# R2P_Proximity_module.net
KiCad netlist of a schematic drawn in EAGLE
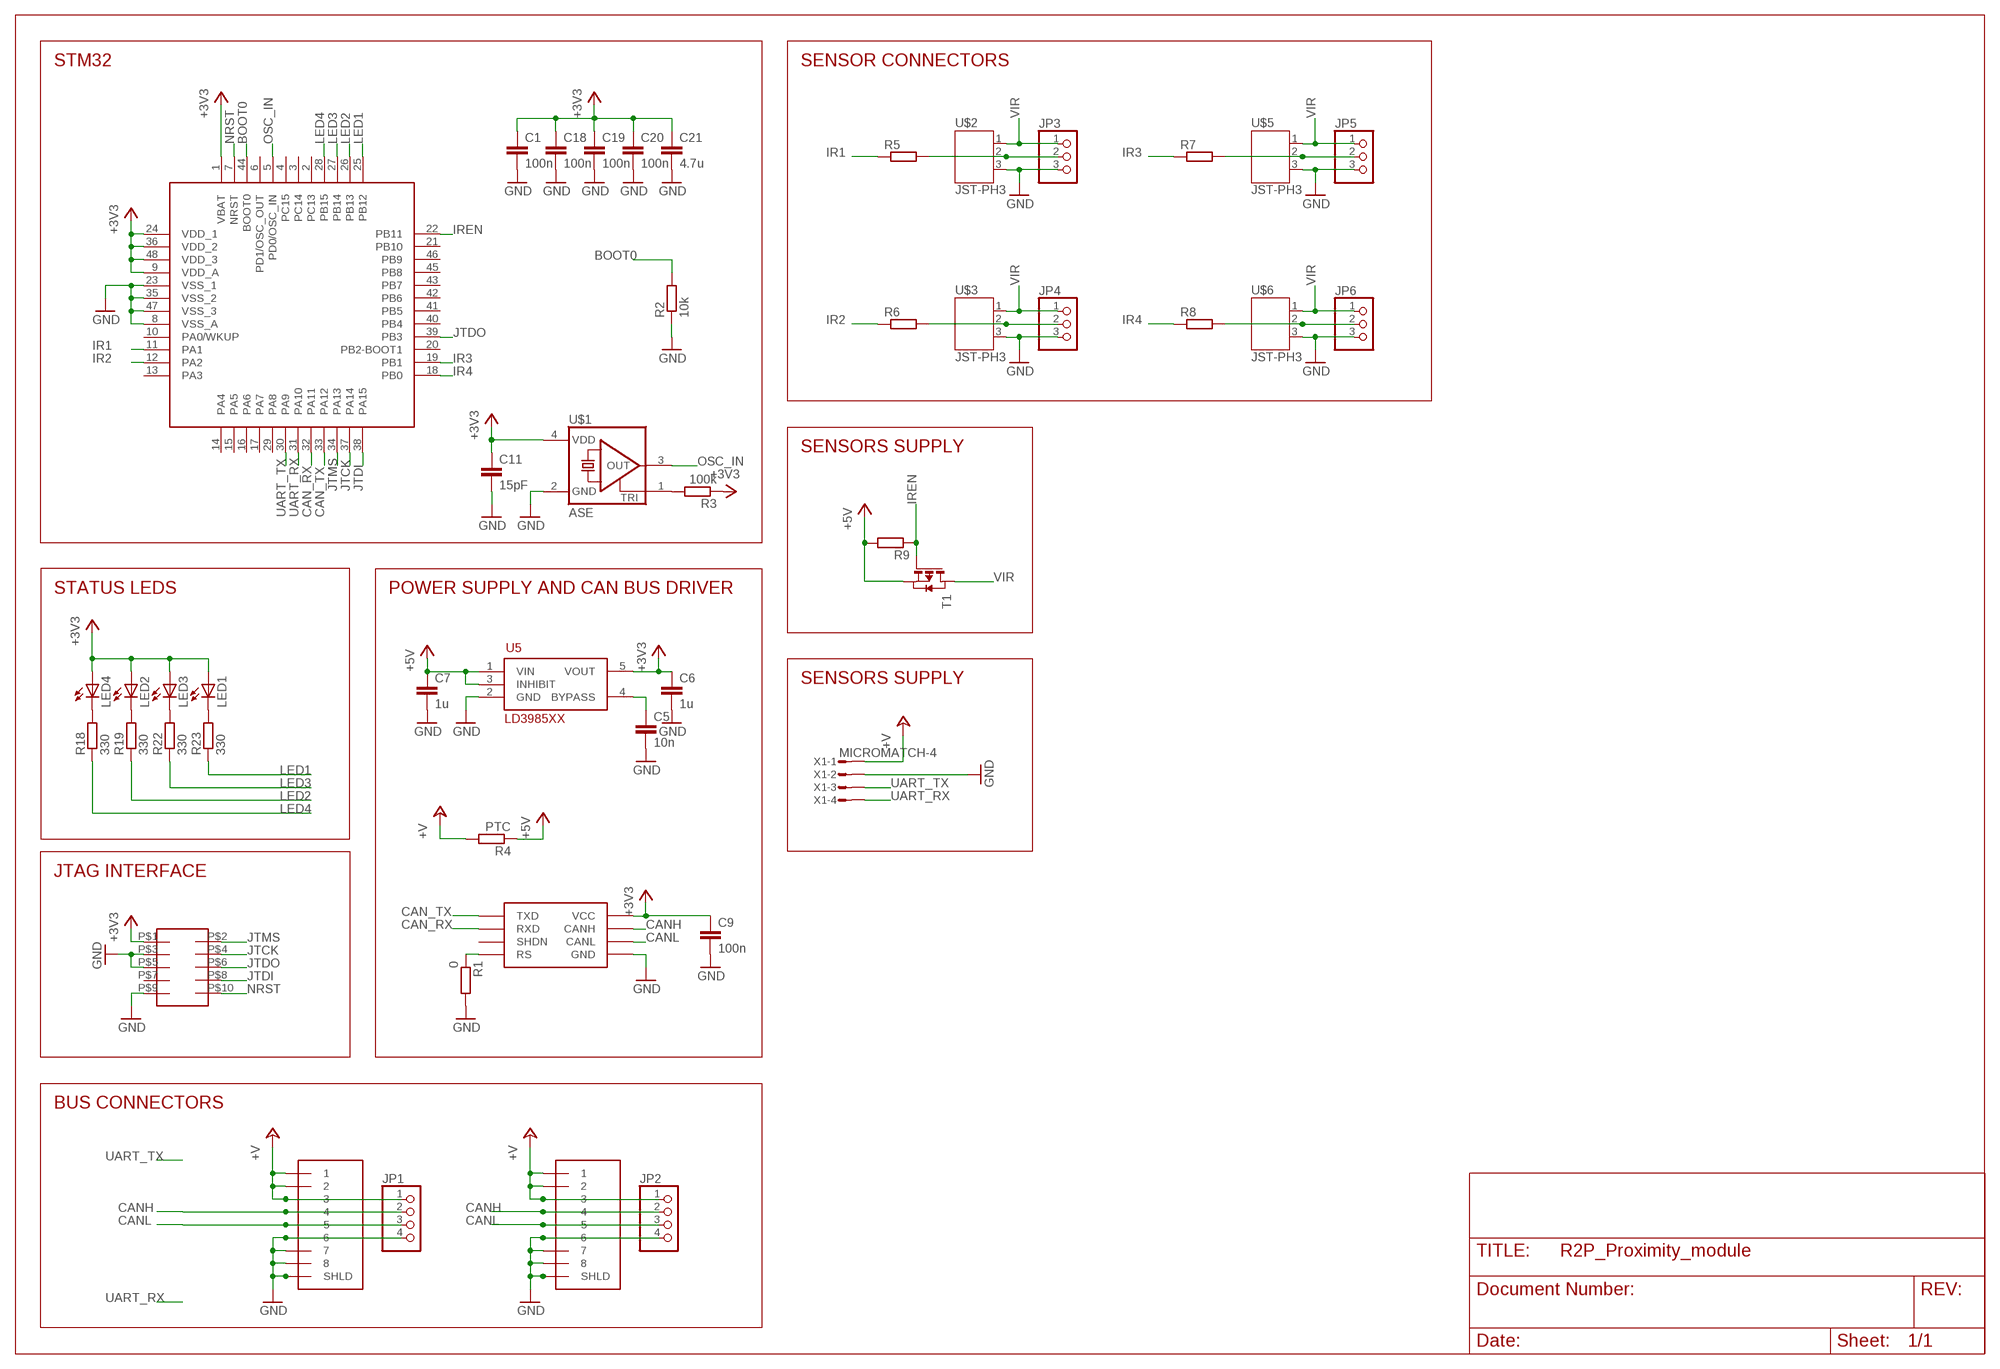
[diagram p0: schematic, sheet 1]

(export (version "E")
  (design (tool "Eeschema 10.0.6"))
  (components
    (comp (ref "1")
      (value "RJ45-43860")
      (footprint "eagle-import:0438600010")
      (libsource (lib "eagle-import") (part "RJ45-43860"))
    )
    (comp (ref "2")
      (value "RJ45-43860")
      (footprint "eagle-import:0438600010")
      (libsource (lib "eagle-import") (part "RJ45-43860"))
    )
    (comp (ref "C1")
      (value "100n")
      (footprint "eagle-import:C0603")
      (libsource (lib "eagle-import") (part "C-EUC0603"))
    )
    (comp (ref "C5")
      (value "10n")
      (footprint "eagle-import:C0603")
      (libsource (lib "eagle-import") (part "C-EUC0603"))
    )
    (comp (ref "C6")
      (value "1u")
      (footprint "eagle-import:C0603")
      (libsource (lib "eagle-import") (part "C-EUC0603"))
    )
    (comp (ref "C7")
      (value "1u")
      (footprint "eagle-import:C0603")
      (libsource (lib "eagle-import") (part "C-EUC0603"))
    )
    (comp (ref "C9")
      (value "100n")
      (footprint "eagle-import:C0603")
      (libsource (lib "eagle-import") (part "C-EUC0603"))
    )
    (comp (ref "C11")
      (value "15pF")
      (footprint "eagle-import:C0603")
      (libsource (lib "eagle-import") (part "C-EUC0603"))
    )
    (comp (ref "C18")
      (value "100n")
      (footprint "eagle-import:C0603")
      (libsource (lib "eagle-import") (part "C-EUC0603"))
    )
    (comp (ref "C19")
      (value "100n")
      (footprint "eagle-import:C0603")
      (libsource (lib "eagle-import") (part "C-EUC0603"))
    )
    (comp (ref "C20")
      (value "100n")
      (footprint "eagle-import:C0603")
      (libsource (lib "eagle-import") (part "C-EUC0603"))
    )
    (comp (ref "C21")
      (value "4.7u")
      (footprint "eagle-import:C0805")
      (libsource (lib "eagle-import") (part "C-EUC0805"))
    )
    (comp (ref "JP1")
      (value "PINHD-1X4")
      (footprint "eagle-import:1X04")
      (libsource (lib "eagle-import") (part "PINHD-1X4"))
    )
    (comp (ref "JP2")
      (value "PINHD-1X4")
      (footprint "eagle-import:1X04")
      (libsource (lib "eagle-import") (part "PINHD-1X4"))
    )
    (comp (ref "JP3")
      (value "PINHD-1X3")
      (footprint "eagle-import:1X03")
      (libsource (lib "eagle-import") (part "PINHD-1X3"))
    )
    (comp (ref "JP4")
      (value "PINHD-1X3")
      (footprint "eagle-import:1X03")
      (libsource (lib "eagle-import") (part "PINHD-1X3"))
    )
    (comp (ref "JP5")
      (value "PINHD-1X3")
      (footprint "eagle-import:1X03")
      (libsource (lib "eagle-import") (part "PINHD-1X3"))
    )
    (comp (ref "JP6")
      (value "PINHD-1X3")
      (footprint "eagle-import:1X03")
      (libsource (lib "eagle-import") (part "PINHD-1X3"))
    )
    (comp (ref "LED1")
      (value "LEDCHIPLED_0805")
      (footprint "eagle-import:CHIPLED_0805")
      (libsource (lib "eagle-import") (part "LEDCHIPLED_0805"))
    )
    (comp (ref "LED2")
      (value "LEDCHIPLED_0805")
      (footprint "eagle-import:CHIPLED_0805")
      (libsource (lib "eagle-import") (part "LEDCHIPLED_0805"))
    )
    (comp (ref "LED3")
      (value "LEDCHIPLED_0805")
      (footprint "eagle-import:CHIPLED_0805")
      (libsource (lib "eagle-import") (part "LEDCHIPLED_0805"))
    )
    (comp (ref "LED4")
      (value "LEDCHIPLED_0805")
      (footprint "eagle-import:CHIPLED_0805")
      (libsource (lib "eagle-import") (part "LEDCHIPLED_0805"))
    )
    (comp (ref "R1")
      (value "0")
      (footprint "eagle-import:R0603")
      (libsource (lib "eagle-import") (part "R-EU_R0603"))
    )
    (comp (ref "R2")
      (value "10k")
      (footprint "eagle-import:R0603")
      (libsource (lib "eagle-import") (part "R-EU_R0603"))
    )
    (comp (ref "R3")
      (value "100k")
      (footprint "eagle-import:R0603")
      (libsource (lib "eagle-import") (part "R-EU_R0603"))
    )
    (comp (ref "R4")
      (value "PTC")
      (footprint "eagle-import:R0603")
      (libsource (lib "eagle-import") (part "R-EU_R0603"))
    )
    (comp (ref "R5")
      (value "R-EU_R0603")
      (footprint "eagle-import:R0603")
      (libsource (lib "eagle-import") (part "R-EU_R0603"))
    )
    (comp (ref "R6")
      (value "R-EU_R0603")
      (footprint "eagle-import:R0603")
      (libsource (lib "eagle-import") (part "R-EU_R0603"))
    )
    (comp (ref "R7")
      (value "R-EU_R0603")
      (footprint "eagle-import:R0603")
      (libsource (lib "eagle-import") (part "R-EU_R0603"))
    )
    (comp (ref "R8")
      (value "R-EU_R0603")
      (footprint "eagle-import:R0603")
      (libsource (lib "eagle-import") (part "R-EU_R0603"))
    )
    (comp (ref "R9")
      (value "R-EU_R0603")
      (footprint "eagle-import:R0603")
      (libsource (lib "eagle-import") (part "R-EU_R0603"))
    )
    (comp (ref "R18")
      (value "330")
      (footprint "eagle-import:R0603")
      (libsource (lib "eagle-import") (part "R-EU_R0603"))
    )
    (comp (ref "R19")
      (value "330")
      (footprint "eagle-import:R0603")
      (libsource (lib "eagle-import") (part "R-EU_R0603"))
    )
    (comp (ref "R22")
      (value "330")
      (footprint "eagle-import:R0603")
      (libsource (lib "eagle-import") (part "R-EU_R0603"))
    )
    (comp (ref "R23")
      (value "330")
      (footprint "eagle-import:R0603")
      (libsource (lib "eagle-import") (part "R-EU_R0603"))
    )
    (comp (ref "SOT1")
      (value "MAX3051")
      (footprint "eagle-import:SOT23-8L")
      (libsource (lib "eagle-import") (part "MAX3051"))
    )
    (comp (ref "T1")
      (value "PMOSSOT23")
      (footprint "eagle-import:SOT-23")
      (libsource (lib "eagle-import") (part "PMOSSOT23"))
    )
    (comp (ref "U$1")
      (value "ASE")
      (footprint "eagle-import:ASE")
      (libsource (lib "eagle-import") (part "ASE"))
    )
    (comp (ref "U$2")
      (value "JST-PH3")
      (footprint "eagle-import:JST-PH3")
      (libsource (lib "eagle-import") (part "JST-PH3"))
    )
    (comp (ref "U$3")
      (value "JST-PH3")
      (footprint "eagle-import:JST-PH3")
      (libsource (lib "eagle-import") (part "JST-PH3"))
    )
    (comp (ref "U$4")
      (value "FTSH-105")
      (footprint "eagle-import:FTSH-105")
      (libsource (lib "eagle-import") (part "FTSH-105"))
    )
    (comp (ref "U$5")
      (value "JST-PH3")
      (footprint "eagle-import:JST-PH3")
      (libsource (lib "eagle-import") (part "JST-PH3"))
    )
    (comp (ref "U$6")
      (value "JST-PH3")
      (footprint "eagle-import:JST-PH3")
      (libsource (lib "eagle-import") (part "JST-PH3"))
    )
    (comp (ref "U1")
      (value "STM32F103CX")
      (footprint "eagle-import:LQFP48")
      (libsource (lib "eagle-import") (part "STM32F103CX"))
    )
    (comp (ref "U5")
      (value "LD3985XX")
      (footprint "eagle-import:SOT23-5L")
      (libsource (lib "eagle-import") (part "LD3985XX"))
    )
    (comp (ref "X1")
      (value "MICROMATCH-4")
      (footprint "eagle-import:MICROMATCH-4")
      (libsource (lib "eagle-import") (part "MICROMATCH-4"))
    )
  )
  (nets
    (net (code "1") (name "+3V3") (class "Default")
      (node (ref "C1") (pin "1") (pinfunction "1_1") (pintype "passive"))
      (node (ref "C11") (pin "1") (pinfunction "1_1") (pintype "passive"))
      (node (ref "C18") (pin "1") (pinfunction "1_1") (pintype "passive"))
      (node (ref "C19") (pin "1") (pinfunction "1_1") (pintype "passive"))
      (node (ref "C20") (pin "1") (pinfunction "1_1") (pintype "passive"))
      (node (ref "C21") (pin "1") (pinfunction "1_1") (pintype "passive"))
      (node (ref "C6") (pin "1") (pinfunction "1_1") (pintype "passive"))
      (node (ref "C9") (pin "1") (pinfunction "1_1") (pintype "passive"))
      (node (ref "LED1") (pin "A") (pinfunction "A_A") (pintype "passive"))
      (node (ref "LED2") (pin "A") (pinfunction "A_A") (pintype "passive"))
      (node (ref "LED3") (pin "A") (pinfunction "A_A") (pintype "passive"))
      (node (ref "LED4") (pin "A") (pinfunction "A_A") (pintype "passive"))
      (node (ref "R3") (pin "1") (pinfunction "1_1") (pintype "passive"))
      (node (ref "SOT1") (pin "P$3") (pinfunction "VCC_P$3") (pintype "bidirectional"))
      (node (ref "U$1") (pin "4") (pinfunction "VDD_4") (pintype "power_in"))
      (node (ref "U$4") (pin "P$1") (pinfunction "P$1_P$1") (pintype "bidirectional"))
      (node (ref "U1") (pin "1") (pinfunction "VBAT_1") (pintype "bidirectional"))
      (node (ref "U1") (pin "24") (pinfunction "VDD_1_24") (pintype "bidirectional"))
      (node (ref "U1") (pin "36") (pinfunction "VDD_2_36") (pintype "bidirectional"))
      (node (ref "U1") (pin "48") (pinfunction "VDD_3_48") (pintype "bidirectional"))
      (node (ref "U1") (pin "9") (pinfunction "VDD_A_9") (pintype "bidirectional"))
      (node (ref "U5") (pin "5") (pinfunction "VOUT_5") (pintype "bidirectional"))
    )
    (net (code "2") (name "+5V") (class "Default")
      (node (ref "C7") (pin "1") (pinfunction "1_1") (pintype "passive"))
      (node (ref "R4") (pin "1") (pinfunction "1_1") (pintype "passive"))
      (node (ref "R9") (pin "2") (pinfunction "2_2") (pintype "passive"))
      (node (ref "T1") (pin "2") (pinfunction "S_2") (pintype "passive"))
      (node (ref "U5") (pin "1") (pinfunction "VIN_1") (pintype "bidirectional"))
      (node (ref "U5") (pin "3") (pinfunction "INHIBIT_3") (pintype "bidirectional"))
    )
    (net (code "3") (name "+V") (class "Default")
      (node (ref "1") (pin "P$1") (pinfunction "1_P$1") (pintype "bidirectional"))
      (node (ref "1") (pin "P$2") (pinfunction "2_P$2") (pintype "bidirectional"))
      (node (ref "1") (pin "P$3") (pinfunction "3_P$3") (pintype "bidirectional"))
      (node (ref "2") (pin "P$1") (pinfunction "1_P$1") (pintype "bidirectional"))
      (node (ref "2") (pin "P$2") (pinfunction "2_P$2") (pintype "bidirectional"))
      (node (ref "2") (pin "P$3") (pinfunction "3_P$3") (pintype "bidirectional"))
      (node (ref "JP1") (pin "1") (pinfunction "1_1") (pintype "passive"))
      (node (ref "JP2") (pin "1") (pinfunction "1_1") (pintype "passive"))
      (node (ref "R4") (pin "2") (pinfunction "2_2") (pintype "passive"))
      (node (ref "X1") (pin "1") (pinfunction "S_1") (pintype "passive"))
    )
    (net (code "4") (name "/BOOT0") (class "Default")
      (node (ref "R2") (pin "2") (pinfunction "2_2") (pintype "passive"))
      (node (ref "U1") (pin "44") (pinfunction "BOOT0_44") (pintype "bidirectional"))
    )
    (net (code "5") (name "/CANH") (class "Default")
      (node (ref "1") (pin "P$4") (pinfunction "4_P$4") (pintype "bidirectional"))
      (node (ref "2") (pin "P$4") (pinfunction "4_P$4") (pintype "bidirectional"))
      (node (ref "JP1") (pin "2") (pinfunction "2_2") (pintype "passive"))
      (node (ref "JP2") (pin "2") (pinfunction "2_2") (pintype "passive"))
      (node (ref "SOT1") (pin "P$7") (pinfunction "CANH_P$7") (pintype "bidirectional"))
    )
    (net (code "6") (name "/CANL") (class "Default")
      (node (ref "1") (pin "P$5") (pinfunction "5_P$5") (pintype "bidirectional"))
      (node (ref "2") (pin "P$5") (pinfunction "5_P$5") (pintype "bidirectional"))
      (node (ref "JP1") (pin "3") (pinfunction "3_3") (pintype "passive"))
      (node (ref "JP2") (pin "3") (pinfunction "3_3") (pintype "passive"))
      (node (ref "SOT1") (pin "P$6") (pinfunction "CANL_P$6") (pintype "bidirectional"))
    )
    (net (code "7") (name "/CAN_RX") (class "Default")
      (node (ref "SOT1") (pin "P$4") (pinfunction "RXD_P$4") (pintype "bidirectional"))
      (node (ref "U1") (pin "32") (pinfunction "PA11_32") (pintype "bidirectional"))
    )
    (net (code "8") (name "/CAN_TX") (class "Default")
      (node (ref "SOT1") (pin "P$1") (pinfunction "TXD_P$1") (pintype "bidirectional"))
      (node (ref "U1") (pin "33") (pinfunction "PA12_33") (pintype "bidirectional"))
    )
    (net (code "9") (name "/IR1") (class "Default")
      (node (ref "R5") (pin "1") (pinfunction "1_1") (pintype "passive"))
      (node (ref "U1") (pin "11") (pinfunction "PA1_11") (pintype "bidirectional"))
    )
    (net (code "10") (name "/IR2") (class "Default")
      (node (ref "R6") (pin "1") (pinfunction "1_1") (pintype "passive"))
      (node (ref "U1") (pin "12") (pinfunction "PA2_12") (pintype "bidirectional"))
    )
    (net (code "11") (name "/IR3") (class "Default")
      (node (ref "R7") (pin "1") (pinfunction "1_1") (pintype "passive"))
      (node (ref "U1") (pin "19") (pinfunction "PB1_19") (pintype "bidirectional"))
    )
    (net (code "12") (name "/IR4") (class "Default")
      (node (ref "R8") (pin "1") (pinfunction "1_1") (pintype "passive"))
      (node (ref "U1") (pin "18") (pinfunction "PB0_18") (pintype "bidirectional"))
    )
    (net (code "13") (name "/IREN") (class "Default")
      (node (ref "R9") (pin "1") (pinfunction "1_1") (pintype "passive"))
      (node (ref "T1") (pin "3") (pinfunction "G_3") (pintype "passive"))
      (node (ref "U1") (pin "22") (pinfunction "PB11_22") (pintype "bidirectional"))
    )
    (net (code "14") (name "/JTCK") (class "Default")
      (node (ref "U$4") (pin "P$4") (pinfunction "P$4_P$4") (pintype "bidirectional"))
      (node (ref "U1") (pin "37") (pinfunction "PA14_37") (pintype "bidirectional"))
    )
    (net (code "15") (name "/JTDI") (class "Default")
      (node (ref "U$4") (pin "P$8") (pinfunction "P$8_P$8") (pintype "bidirectional"))
      (node (ref "U1") (pin "38") (pinfunction "PA15_38") (pintype "bidirectional"))
    )
    (net (code "16") (name "/JTDO") (class "Default")
      (node (ref "U$4") (pin "P$6") (pinfunction "P$6_P$6") (pintype "bidirectional"))
      (node (ref "U1") (pin "39") (pinfunction "PB3_39") (pintype "bidirectional"))
    )
    (net (code "17") (name "/JTMS") (class "Default")
      (node (ref "U$4") (pin "P$2") (pinfunction "P$2_P$2") (pintype "bidirectional"))
      (node (ref "U1") (pin "34") (pinfunction "PA13_34") (pintype "bidirectional"))
    )
    (net (code "18") (name "/LED1") (class "Default")
      (node (ref "R23") (pin "1") (pinfunction "1_1") (pintype "passive"))
      (node (ref "U1") (pin "25") (pinfunction "PB12_25") (pintype "bidirectional"))
    )
    (net (code "19") (name "/LED2") (class "Default")
      (node (ref "R19") (pin "1") (pinfunction "1_1") (pintype "passive"))
      (node (ref "U1") (pin "26") (pinfunction "PB13_26") (pintype "bidirectional"))
    )
    (net (code "20") (name "/LED3") (class "Default")
      (node (ref "R22") (pin "1") (pinfunction "1_1") (pintype "passive"))
      (node (ref "U1") (pin "27") (pinfunction "PB14_27") (pintype "bidirectional"))
    )
    (net (code "21") (name "/LED4") (class "Default")
      (node (ref "R18") (pin "1") (pinfunction "1_1") (pintype "passive"))
      (node (ref "U1") (pin "28") (pinfunction "PB15_28") (pintype "bidirectional"))
    )
    (net (code "22") (name "/NRST") (class "Default")
      (node (ref "U$4") (pin "P$10") (pinfunction "P$10_P$10") (pintype "bidirectional"))
      (node (ref "U1") (pin "7") (pinfunction "NRST_7") (pintype "bidirectional"))
    )
    (net (code "23") (name "/OSC_IN") (class "Default")
      (node (ref "U$1") (pin "3") (pinfunction "OUT_3") (pintype "output"))
      (node (ref "U1") (pin "5") (pinfunction "PD0/OSC_IN_5") (pintype "bidirectional"))
    )
    (net (code "24") (name "/UART_RX") (class "Default")
      (node (ref "U1") (pin "31") (pinfunction "PA10_31") (pintype "bidirectional"))
      (node (ref "X1") (pin "4") (pinfunction "S_4") (pintype "passive"))
    )
    (net (code "25") (name "/UART_TX") (class "Default")
      (node (ref "U1") (pin "30") (pinfunction "PA9_30") (pintype "bidirectional"))
      (node (ref "X1") (pin "3") (pinfunction "S_3") (pintype "passive"))
    )
    (net (code "26") (name "/VIR") (class "Default")
      (node (ref "JP3") (pin "1") (pinfunction "1_1") (pintype "passive"))
      (node (ref "JP4") (pin "1") (pinfunction "1_1") (pintype "passive"))
      (node (ref "JP5") (pin "1") (pinfunction "1_1") (pintype "passive"))
      (node (ref "JP6") (pin "1") (pinfunction "1_1") (pintype "passive"))
      (node (ref "T1") (pin "1") (pinfunction "D_1") (pintype "passive"))
      (node (ref "U$2") (pin "1") (pinfunction "1_1") (pintype "passive"))
      (node (ref "U$3") (pin "1") (pinfunction "1_1") (pintype "passive"))
      (node (ref "U$5") (pin "1") (pinfunction "1_1") (pintype "passive"))
      (node (ref "U$6") (pin "1") (pinfunction "1_1") (pintype "passive"))
    )
    (net (code "27") (name "GND") (class "Default")
      (node (ref "1") (pin "P$10") (pinfunction "P$1_P$10") (pintype "power_in"))
      (node (ref "1") (pin "P$6") (pinfunction "6_P$6") (pintype "bidirectional"))
      (node (ref "1") (pin "P$7") (pinfunction "7_P$7") (pintype "bidirectional"))
      (node (ref "1") (pin "P$8") (pinfunction "8_P$8") (pintype "bidirectional"))
      (node (ref "1") (pin "P$9") (pinfunction "SHLD_P$9") (pintype "power_in"))
      (node (ref "2") (pin "P$10") (pinfunction "P$1_P$10") (pintype "power_in"))
      (node (ref "2") (pin "P$6") (pinfunction "6_P$6") (pintype "bidirectional"))
      (node (ref "2") (pin "P$7") (pinfunction "7_P$7") (pintype "bidirectional"))
      (node (ref "2") (pin "P$8") (pinfunction "8_P$8") (pintype "bidirectional"))
      (node (ref "2") (pin "P$9") (pinfunction "SHLD_P$9") (pintype "power_in"))
      (node (ref "C1") (pin "2") (pinfunction "2_2") (pintype "passive"))
      (node (ref "C11") (pin "2") (pinfunction "2_2") (pintype "passive"))
      (node (ref "C18") (pin "2") (pinfunction "2_2") (pintype "passive"))
      (node (ref "C19") (pin "2") (pinfunction "2_2") (pintype "passive"))
      (node (ref "C20") (pin "2") (pinfunction "2_2") (pintype "passive"))
      (node (ref "C21") (pin "2") (pinfunction "2_2") (pintype "passive"))
      (node (ref "C5") (pin "2") (pinfunction "2_2") (pintype "passive"))
      (node (ref "C6") (pin "2") (pinfunction "2_2") (pintype "passive"))
      (node (ref "C7") (pin "2") (pinfunction "2_2") (pintype "passive"))
      (node (ref "C9") (pin "2") (pinfunction "2_2") (pintype "passive"))
      (node (ref "JP1") (pin "4") (pinfunction "4_4") (pintype "passive"))
      (node (ref "JP2") (pin "4") (pinfunction "4_4") (pintype "passive"))
      (node (ref "JP3") (pin "3") (pinfunction "3_3") (pintype "passive"))
      (node (ref "JP4") (pin "3") (pinfunction "3_3") (pintype "passive"))
      (node (ref "JP5") (pin "3") (pinfunction "3_3") (pintype "passive"))
      (node (ref "JP6") (pin "3") (pinfunction "3_3") (pintype "passive"))
      (node (ref "R1") (pin "2") (pinfunction "2_2") (pintype "passive"))
      (node (ref "R2") (pin "1") (pinfunction "1_1") (pintype "passive"))
      (node (ref "SOT1") (pin "P$2") (pinfunction "GND_P$2") (pintype "bidirectional"))
      (node (ref "U$1") (pin "2") (pinfunction "GND_2") (pintype "power_in"))
      (node (ref "U$2") (pin "3") (pinfunction "3_3") (pintype "passive"))
      (node (ref "U$3") (pin "3") (pinfunction "3_3") (pintype "passive"))
      (node (ref "U$4") (pin "P$3") (pinfunction "P$3_P$3") (pintype "bidirectional"))
      (node (ref "U$4") (pin "P$5") (pinfunction "P$5_P$5") (pintype "bidirectional"))
      (node (ref "U$4") (pin "P$9") (pinfunction "P$9_P$9") (pintype "bidirectional"))
      (node (ref "U$5") (pin "3") (pinfunction "3_3") (pintype "passive"))
      (node (ref "U$6") (pin "3") (pinfunction "3_3") (pintype "passive"))
      (node (ref "U1") (pin "23") (pinfunction "VSS_1_23") (pintype "bidirectional"))
      (node (ref "U1") (pin "35") (pinfunction "VSS_2_35") (pintype "bidirectional"))
      (node (ref "U1") (pin "47") (pinfunction "VSS_3_47") (pintype "bidirectional"))
      (node (ref "U1") (pin "8") (pinfunction "VSS_A_8") (pintype "bidirectional"))
      (node (ref "U5") (pin "2") (pinfunction "GND_2") (pintype "bidirectional"))
      (node (ref "X1") (pin "2") (pinfunction "S_2") (pintype "passive"))
    )
    (net (code "28") (name "Net-(JP3-Pad2)") (class "Default")
      (node (ref "JP3") (pin "2") (pinfunction "2_2") (pintype "passive"))
      (node (ref "R5") (pin "2") (pinfunction "2_2") (pintype "passive"))
      (node (ref "U$2") (pin "2") (pinfunction "2_2") (pintype "passive"))
    )
    (net (code "29") (name "Net-(JP4-Pad2)") (class "Default")
      (node (ref "JP4") (pin "2") (pinfunction "2_2") (pintype "passive"))
      (node (ref "R6") (pin "2") (pinfunction "2_2") (pintype "passive"))
      (node (ref "U$3") (pin "2") (pinfunction "2_2") (pintype "passive"))
    )
    (net (code "30") (name "Net-(JP5-Pad2)") (class "Default")
      (node (ref "JP5") (pin "2") (pinfunction "2_2") (pintype "passive"))
      (node (ref "R7") (pin "2") (pinfunction "2_2") (pintype "passive"))
      (node (ref "U$5") (pin "2") (pinfunction "2_2") (pintype "passive"))
    )
    (net (code "31") (name "Net-(JP6-Pad2)") (class "Default")
      (node (ref "JP6") (pin "2") (pinfunction "2_2") (pintype "passive"))
      (node (ref "R8") (pin "2") (pinfunction "2_2") (pintype "passive"))
      (node (ref "U$6") (pin "2") (pinfunction "2_2") (pintype "passive"))
    )
    (net (code "32") (name "Net-(LED1-PadC)") (class "Default")
      (node (ref "LED1") (pin "C") (pinfunction "C_C") (pintype "passive"))
      (node (ref "R23") (pin "2") (pinfunction "2_2") (pintype "passive"))
    )
    (net (code "33") (name "Net-(LED2-PadC)") (class "Default")
      (node (ref "LED2") (pin "C") (pinfunction "C_C") (pintype "passive"))
      (node (ref "R19") (pin "2") (pinfunction "2_2") (pintype "passive"))
    )
    (net (code "34") (name "Net-(LED3-PadC)") (class "Default")
      (node (ref "LED3") (pin "C") (pinfunction "C_C") (pintype "passive"))
      (node (ref "R22") (pin "2") (pinfunction "2_2") (pintype "passive"))
    )
    (net (code "35") (name "Net-(LED4-PadC)") (class "Default")
      (node (ref "LED4") (pin "C") (pinfunction "C_C") (pintype "passive"))
      (node (ref "R18") (pin "2") (pinfunction "2_2") (pintype "passive"))
    )
    (net (code "36") (name "Net-(SOT1-RS)") (class "Default")
      (node (ref "R1") (pin "1") (pinfunction "1_1") (pintype "passive"))
      (node (ref "SOT1") (pin "P$8") (pinfunction "RS_P$8") (pintype "bidirectional"))
    )
    (net (code "37") (name "Net-(U$1-TRI)") (class "Default")
      (node (ref "R3") (pin "2") (pinfunction "2_2") (pintype "passive"))
      (node (ref "U$1") (pin "1") (pinfunction "TRI_1") (pintype "input"))
    )
    (net (code "38") (name "Net-(U5-BYPASS)") (class "Default")
      (node (ref "C5") (pin "1") (pinfunction "1_1") (pintype "passive"))
      (node (ref "U5") (pin "4") (pinfunction "BYPASS_4") (pintype "bidirectional"))
    )
    (net (code "39") (name "unconnected-(SOT1-SHDN-PadP$5)") (class "Default")
      (node (ref "SOT1") (pin "P$5") (pinfunction "SHDN_P$5") (pintype "bidirectional"))
    )
    (net (code "40") (name "unconnected-(U$4-PadP$7)") (class "Default")
      (node (ref "U$4") (pin "P$7") (pinfunction "P$7_P$7") (pintype "bidirectional"))
    )
    (net (code "41") (name "unconnected-(U1-PA0{slash}WKUP-Pad10)") (class "Default")
      (node (ref "U1") (pin "10") (pinfunction "PA0/WKUP_10") (pintype "bidirectional"))
    )
    (net (code "42") (name "unconnected-(U1-PA3-Pad13)") (class "Default")
      (node (ref "U1") (pin "13") (pinfunction "PA3_13") (pintype "bidirectional"))
    )
    (net (code "43") (name "unconnected-(U1-PA4-Pad14)") (class "Default")
      (node (ref "U1") (pin "14") (pinfunction "PA4_14") (pintype "bidirectional"))
    )
    (net (code "44") (name "unconnected-(U1-PA5-Pad15)") (class "Default")
      (node (ref "U1") (pin "15") (pinfunction "PA5_15") (pintype "bidirectional"))
    )
    (net (code "45") (name "unconnected-(U1-PA6-Pad16)") (class "Default")
      (node (ref "U1") (pin "16") (pinfunction "PA6_16") (pintype "bidirectional"))
    )
    (net (code "46") (name "unconnected-(U1-PA7-Pad17)") (class "Default")
      (node (ref "U1") (pin "17") (pinfunction "PA7_17") (pintype "bidirectional"))
    )
    (net (code "47") (name "unconnected-(U1-PA8-Pad29)") (class "Default")
      (node (ref "U1") (pin "29") (pinfunction "PA8_29") (pintype "bidirectional"))
    )
    (net (code "48") (name "unconnected-(U1-PB2-BOOT1-Pad20)") (class "Default")
      (node (ref "U1") (pin "20") (pinfunction "PB2-BOOT1_20") (pintype "bidirectional"))
    )
    (net (code "49") (name "unconnected-(U1-PB4-Pad40)") (class "Default")
      (node (ref "U1") (pin "40") (pinfunction "PB4_40") (pintype "bidirectional"))
    )
    (net (code "50") (name "unconnected-(U1-PB5-Pad41)") (class "Default")
      (node (ref "U1") (pin "41") (pinfunction "PB5_41") (pintype "bidirectional"))
    )
    (net (code "51") (name "unconnected-(U1-PB6-Pad42)") (class "Default")
      (node (ref "U1") (pin "42") (pinfunction "PB6_42") (pintype "bidirectional"))
    )
    (net (code "52") (name "unconnected-(U1-PB7-Pad43)") (class "Default")
      (node (ref "U1") (pin "43") (pinfunction "PB7_43") (pintype "bidirectional"))
    )
    (net (code "53") (name "unconnected-(U1-PB8-Pad45)") (class "Default")
      (node (ref "U1") (pin "45") (pinfunction "PB8_45") (pintype "bidirectional"))
    )
    (net (code "54") (name "unconnected-(U1-PB9-Pad46)") (class "Default")
      (node (ref "U1") (pin "46") (pinfunction "PB9_46") (pintype "bidirectional"))
    )
    (net (code "55") (name "unconnected-(U1-PB10-Pad21)") (class "Default")
      (node (ref "U1") (pin "21") (pinfunction "PB10_21") (pintype "bidirectional"))
    )
    (net (code "56") (name "unconnected-(U1-PC13-Pad2)") (class "Default")
      (node (ref "U1") (pin "2") (pinfunction "PC13_2") (pintype "bidirectional"))
    )
    (net (code "57") (name "unconnected-(U1-PC14-Pad3)") (class "Default")
      (node (ref "U1") (pin "3") (pinfunction "PC14_3") (pintype "bidirectional"))
    )
    (net (code "58") (name "unconnected-(U1-PC15-Pad4)") (class "Default")
      (node (ref "U1") (pin "4") (pinfunction "PC15_4") (pintype "bidirectional"))
    )
    (net (code "59") (name "unconnected-(U1-PD1{slash}OSC_OUT-Pad6)") (class "Default")
      (node (ref "U1") (pin "6") (pinfunction "PD1/OSC_OUT_6") (pintype "bidirectional"))
    )
  )
)
